# rx_board.net
KiCad netlist of a schematic drawn in Altium Designer
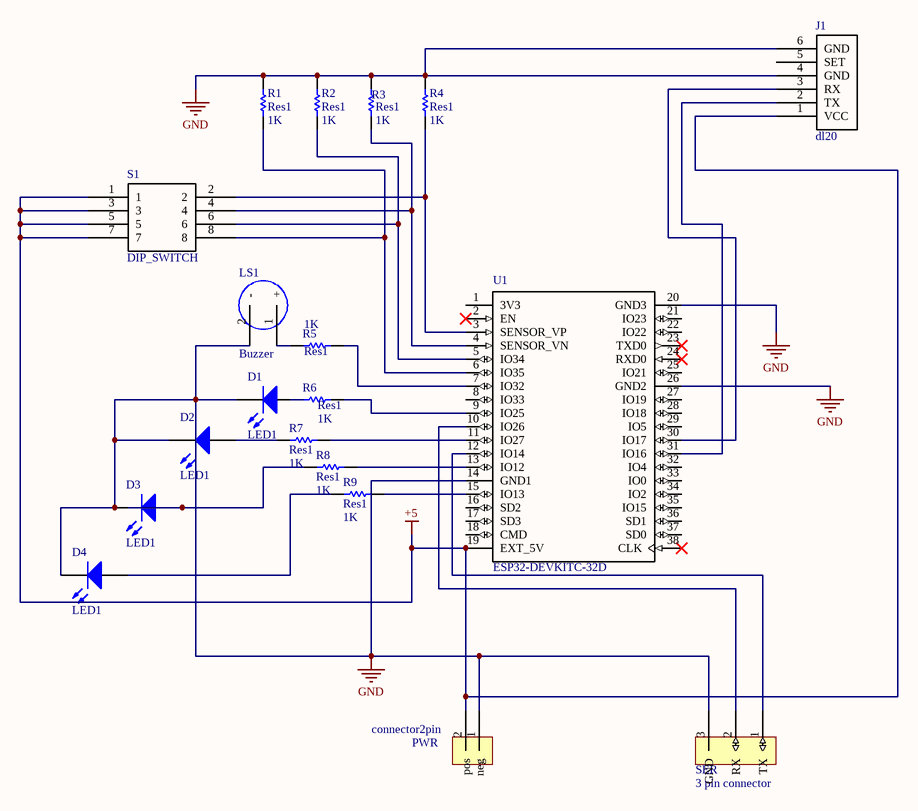
[diagram p0: rx_board.SchDoc]

(export (version "E")
  (design (tool "Eeschema 10.0.6"))
  (components
    (comp (ref "D1")
      (value "LED1")
      (footprint "led3mm")
      (description "Typical RED GaAs LED")
      (fields (field (name "PUBLISHER") "Altium Limited"))
      (libsource (lib "Miscellaneous Devices") (part "LED1"))
    )
    (comp (ref "D2")
      (value "LED1")
      (footprint "led3mm")
      (description "Typical RED GaAs LED")
      (fields (field (name "PUBLISHER") "Altium Limited"))
      (libsource (lib "Miscellaneous Devices") (part "LED1"))
    )
    (comp (ref "D3")
      (value "LED1")
      (footprint "led3mm")
      (description "Typical RED GaAs LED")
      (fields (field (name "PUBLISHER") "Altium Limited"))
      (libsource (lib "Miscellaneous Devices") (part "LED1"))
    )
    (comp (ref "D4")
      (value "LED1")
      (footprint "led3mm")
      (description "Typical RED GaAs LED")
      (fields (field (name "PUBLISHER") "Altium Limited"))
      (libsource (lib "Miscellaneous Devices") (part "LED1"))
    )
    (comp (ref "J1") (value "dl20") (footprint "DL20") (libsource (lib "Schlib1") (part "dl20")))
    (comp (ref "LS1") (value "Buzzer") (footprint "buzzer") (libsource (lib "Buzzer") (part "Buzzer")))
    (comp (ref "PWR")
      (value "connector2pin")
      (footprint "connector2pin")
      (libsource (lib "connector2pin") (part "connector2pin"))
    )
    (comp (ref "R1")
      (value "Res1")
      (footprint "J1-0603")
      (description "Resistor")
      (fields (field (name "ALTIUM_VALUE") "1K") (field (name "PUBLISHER") "Altium Limited"))
      (libsource (lib "Miscellaneous Devices") (part "Res1"))
    )
    (comp (ref "R2")
      (value "Res1")
      (footprint "J1-0603")
      (description "Resistor")
      (fields (field (name "ALTIUM_VALUE") "1K") (field (name "PUBLISHER") "Altium Limited"))
      (libsource (lib "Miscellaneous Devices") (part "Res1"))
    )
    (comp (ref "R3")
      (value "Res1")
      (footprint "J1-0603")
      (description "Resistor")
      (fields (field (name "ALTIUM_VALUE") "1K") (field (name "PUBLISHER") "Altium Limited"))
      (libsource (lib "Miscellaneous Devices") (part "Res1"))
    )
    (comp (ref "R4")
      (value "Res1")
      (footprint "J1-0603")
      (description "Resistor")
      (fields (field (name "ALTIUM_VALUE") "1K") (field (name "PUBLISHER") "Altium Limited"))
      (libsource (lib "Miscellaneous Devices") (part "Res1"))
    )
    (comp (ref "R5")
      (value "Res1")
      (footprint "J1-0603")
      (description "Resistor")
      (fields (field (name "ALTIUM_VALUE") "1K") (field (name "PUBLISHER") "Altium Limited"))
      (libsource (lib "Miscellaneous Devices") (part "Res1"))
    )
    (comp (ref "R6")
      (value "Res1")
      (footprint "J1-0603")
      (description "Resistor")
      (fields (field (name "ALTIUM_VALUE") "1K") (field (name "PUBLISHER") "Altium Limited"))
      (libsource (lib "Miscellaneous Devices") (part "Res1"))
    )
    (comp (ref "R7")
      (value "Res1")
      (footprint "J1-0603")
      (description "Resistor")
      (fields (field (name "ALTIUM_VALUE") "1K") (field (name "PUBLISHER") "Altium Limited"))
      (libsource (lib "Miscellaneous Devices") (part "Res1"))
    )
    (comp (ref "R8")
      (value "Res1")
      (footprint "J1-0603")
      (description "Resistor")
      (fields (field (name "ALTIUM_VALUE") "1K") (field (name "PUBLISHER") "Altium Limited"))
      (libsource (lib "Miscellaneous Devices") (part "Res1"))
    )
    (comp (ref "R9")
      (value "Res1")
      (footprint "J1-0603")
      (description "Resistor")
      (fields (field (name "ALTIUM_VALUE") "1K") (field (name "PUBLISHER") "Altium Limited"))
      (libsource (lib "Miscellaneous Devices") (part "Res1"))
    )
    (comp (ref "S1")
      (value "DIP_SWITCH")
      (footprint "DIP_SWITCH_4_SPST")
      (libsource (lib "Schlib1") (part "DIP_SWITCH"))
    )
    (comp (ref "SER")
      (value "3 pin connector")
      (footprint "connector3pin")
      (libsource (lib "CONNECTOR3PIN") (part "CONNECTOR3PIN"))
    )
    (comp (ref "U1")
      (value "ESP32-DEVKITC-32D")
      (footprint "MODULE_ESP32-DEVKITC-32D")
      (description "Eval Board For Esp-Wroom-32")
      (fields (field (name "MF") "Espressif Systems"))
      (libsource (lib "ESP32-DEVKITC-32D") (part "ESP32-DEVKITC-32D"))
    )
  )
  (nets
    (net (code "1") (name "+5") (class "Default")
      (node (ref "J1") (pin "1") (pinfunction "VCC_1") (pintype "power_in"))
      (node (ref "PWR") (pin "2") (pinfunction "pos_2") (pintype "power_in"))
      (node (ref "S1") (pin "1") (pinfunction "1_1") (pintype "passive"))
      (node (ref "S1") (pin "3") (pinfunction "3_3") (pintype "passive"))
      (node (ref "S1") (pin "5") (pinfunction "5_5") (pintype "passive"))
      (node (ref "S1") (pin "7") (pinfunction "7_7") (pintype "passive"))
      (node (ref "U1") (pin "19") (pinfunction "EXT_5V_19") (pintype "power_in"))
    )
    (net (code "2") (name "GND") (class "Default")
      (node (ref "D1") (pin "2") (pinfunction "K_2") (pintype "passive"))
      (node (ref "D2") (pin "2") (pinfunction "K_2") (pintype "passive"))
      (node (ref "D3") (pin "2") (pinfunction "K_2") (pintype "passive"))
      (node (ref "D4") (pin "2") (pinfunction "K_2") (pintype "passive"))
      (node (ref "J1") (pin "4") (pinfunction "GND_4") (pintype "power_in"))
      (node (ref "J1") (pin "6") (pinfunction "GND_6") (pintype "power_in"))
      (node (ref "LS1") (pin "2") (pinfunction "-_2") (pintype "power_in"))
      (node (ref "PWR") (pin "1") (pinfunction "neg_1") (pintype "power_in"))
      (node (ref "R1") (pin "1") (pinfunction "1_1") (pintype "passive"))
      (node (ref "R2") (pin "1") (pinfunction "1_1") (pintype "passive"))
      (node (ref "R3") (pin "1") (pinfunction "1_1") (pintype "passive"))
      (node (ref "R4") (pin "1") (pinfunction "1_1") (pintype "passive"))
      (node (ref "SER") (pin "3") (pinfunction "GND_3") (pintype "power_in"))
      (node (ref "U1") (pin "14") (pinfunction "GND1_14") (pintype "power_in"))
      (node (ref "U1") (pin "20") (pinfunction "GND3_20") (pintype "power_in"))
      (node (ref "U1") (pin "26") (pinfunction "GND2_26") (pintype "power_in"))
    )
    (net (code "3") (name "Net-(D1-A)") (class "Default")
      (node (ref "D1") (pin "1") (pinfunction "A_1") (pintype "passive"))
      (node (ref "R6") (pin "1") (pinfunction "1_1") (pintype "passive"))
    )
    (net (code "4") (name "Net-(D2-A)") (class "Default")
      (node (ref "D2") (pin "1") (pinfunction "A_1") (pintype "passive"))
      (node (ref "R7") (pin "1") (pinfunction "1_1") (pintype "passive"))
    )
    (net (code "5") (name "Net-(D3-A)") (class "Default")
      (node (ref "D3") (pin "1") (pinfunction "A_1") (pintype "passive"))
      (node (ref "R8") (pin "1") (pinfunction "1_1") (pintype "passive"))
    )
    (net (code "6") (name "Net-(D4-A)") (class "Default")
      (node (ref "D4") (pin "1") (pinfunction "A_1") (pintype "passive"))
      (node (ref "R9") (pin "1") (pinfunction "1_1") (pintype "passive"))
    )
    (net (code "7") (name "Net-(J1-RX)") (class "Default")
      (node (ref "J1") (pin "3") (pinfunction "RX_3") (pintype "passive"))
      (node (ref "U1") (pin "30") (pinfunction "IO17_30") (pintype "bidirectional"))
    )
    (net (code "8") (name "Net-(J1-TX)") (class "Default")
      (node (ref "J1") (pin "2") (pinfunction "TX_2") (pintype "passive"))
      (node (ref "U1") (pin "31") (pinfunction "IO16_31") (pintype "bidirectional"))
    )
    (net (code "9") (name "Net-(LS1-+)") (class "Default")
      (node (ref "LS1") (pin "1") (pinfunction "+_1") (pintype "power_in"))
      (node (ref "R5") (pin "1") (pinfunction "1_1") (pintype "passive"))
    )
    (net (code "10") (name "Net-(SER-RX)") (class "Default")
      (node (ref "SER") (pin "2") (pinfunction "RX_2") (pintype "bidirectional"))
      (node (ref "U1") (pin "10") (pinfunction "IO26_10") (pintype "bidirectional"))
    )
    (net (code "11") (name "Net-(SER-TX)") (class "Default")
      (node (ref "SER") (pin "1") (pinfunction "TX_1") (pintype "bidirectional"))
      (node (ref "U1") (pin "12") (pinfunction "IO14_12") (pintype "bidirectional"))
    )
    (net (code "12") (name "Net-(U1-IO12)") (class "Default")
      (node (ref "R8") (pin "2") (pinfunction "2_2") (pintype "passive"))
      (node (ref "U1") (pin "13") (pinfunction "IO12_13") (pintype "bidirectional"))
    )
    (net (code "13") (name "Net-(U1-IO13)") (class "Default")
      (node (ref "R9") (pin "2") (pinfunction "2_2") (pintype "passive"))
      (node (ref "U1") (pin "15") (pinfunction "IO13_15") (pintype "bidirectional"))
    )
    (net (code "14") (name "Net-(U1-IO25)") (class "Default")
      (node (ref "R6") (pin "2") (pinfunction "2_2") (pintype "passive"))
      (node (ref "U1") (pin "9") (pinfunction "IO25_9") (pintype "bidirectional"))
    )
    (net (code "15") (name "Net-(U1-IO27)") (class "Default")
      (node (ref "R7") (pin "2") (pinfunction "2_2") (pintype "passive"))
      (node (ref "U1") (pin "11") (pinfunction "IO27_11") (pintype "bidirectional"))
    )
    (net (code "16") (name "Net-(U1-IO32)") (class "Default")
      (node (ref "R5") (pin "2") (pinfunction "2_2") (pintype "passive"))
      (node (ref "U1") (pin "7") (pinfunction "IO32_7") (pintype "bidirectional"))
    )
    (net (code "17") (name "Net-(U1-IO34)") (class "Default")
      (node (ref "R2") (pin "2") (pinfunction "2_2") (pintype "passive"))
      (node (ref "S1") (pin "6") (pinfunction "6_6") (pintype "passive"))
      (node (ref "U1") (pin "5") (pinfunction "IO34_5") (pintype "bidirectional"))
    )
    (net (code "18") (name "Net-(U1-IO35)") (class "Default")
      (node (ref "R1") (pin "2") (pinfunction "2_2") (pintype "passive"))
      (node (ref "S1") (pin "8") (pinfunction "8_8") (pintype "passive"))
      (node (ref "U1") (pin "6") (pinfunction "IO35_6") (pintype "bidirectional"))
    )
    (net (code "19") (name "Net-(U1-SENSOR_VN)") (class "Default")
      (node (ref "R3") (pin "2") (pinfunction "2_2") (pintype "passive"))
      (node (ref "S1") (pin "4") (pinfunction "4_4") (pintype "passive"))
      (node (ref "U1") (pin "4") (pinfunction "SENSOR_VN_4") (pintype "input"))
    )
    (net (code "20") (name "Net-(U1-SENSOR_VP)") (class "Default")
      (node (ref "R4") (pin "2") (pinfunction "2_2") (pintype "passive"))
      (node (ref "S1") (pin "2") (pinfunction "2_2") (pintype "passive"))
      (node (ref "U1") (pin "3") (pinfunction "SENSOR_VP_3") (pintype "input"))
    )
    (net (code "21") (name "unconnected-(J1-SET-Pad5)") (class "Default")
      (node (ref "J1") (pin "5") (pinfunction "SET_5") (pintype "passive"))
    )
    (net (code "22") (name "unconnected-(U1-3V3-Pad1)") (class "Default")
      (node (ref "U1") (pin "1") (pinfunction "3V3_1") (pintype "power_in"))
    )
    (net (code "23") (name "unconnected-(U1-CLK-Pad38)") (class "Default")
      (node (ref "U1") (pin "38") (pinfunction "CLK_38") (pintype "input+no_connect"))
    )
    (net (code "24") (name "unconnected-(U1-CMD-Pad18)") (class "Default")
      (node (ref "U1") (pin "18") (pinfunction "CMD_18") (pintype "bidirectional"))
    )
    (net (code "25") (name "unconnected-(U1-EN-Pad2)") (class "Default")
      (node (ref "U1") (pin "2") (pinfunction "EN_2") (pintype "input+no_connect"))
    )
    (net (code "26") (name "unconnected-(U1-IO0-Pad33)") (class "Default")
      (node (ref "U1") (pin "33") (pinfunction "IO0_33") (pintype "bidirectional"))
    )
    (net (code "27") (name "unconnected-(U1-IO2-Pad34)") (class "Default")
      (node (ref "U1") (pin "34") (pinfunction "IO2_34") (pintype "bidirectional"))
    )
    (net (code "28") (name "unconnected-(U1-IO4-Pad32)") (class "Default")
      (node (ref "U1") (pin "32") (pinfunction "IO4_32") (pintype "bidirectional"))
    )
    (net (code "29") (name "unconnected-(U1-IO5-Pad29)") (class "Default")
      (node (ref "U1") (pin "29") (pinfunction "IO5_29") (pintype "bidirectional"))
    )
    (net (code "30") (name "unconnected-(U1-IO15-Pad35)") (class "Default")
      (node (ref "U1") (pin "35") (pinfunction "IO15_35") (pintype "bidirectional"))
    )
    (net (code "31") (name "unconnected-(U1-IO18-Pad28)") (class "Default")
      (node (ref "U1") (pin "28") (pinfunction "IO18_28") (pintype "bidirectional"))
    )
    (net (code "32") (name "unconnected-(U1-IO19-Pad27)") (class "Default")
      (node (ref "U1") (pin "27") (pinfunction "IO19_27") (pintype "bidirectional"))
    )
    (net (code "33") (name "unconnected-(U1-IO21-Pad25)") (class "Default")
      (node (ref "U1") (pin "25") (pinfunction "IO21_25") (pintype "bidirectional"))
    )
    (net (code "34") (name "unconnected-(U1-IO22-Pad22)") (class "Default")
      (node (ref "U1") (pin "22") (pinfunction "IO22_22") (pintype "bidirectional"))
    )
    (net (code "35") (name "unconnected-(U1-IO23-Pad21)") (class "Default")
      (node (ref "U1") (pin "21") (pinfunction "IO23_21") (pintype "bidirectional"))
    )
    (net (code "36") (name "unconnected-(U1-IO33-Pad8)") (class "Default")
      (node (ref "U1") (pin "8") (pinfunction "IO33_8") (pintype "bidirectional"))
    )
    (net (code "37") (name "unconnected-(U1-RXD0-Pad24)") (class "Default")
      (node (ref "U1") (pin "24") (pinfunction "RXD0_24") (pintype "input+no_connect"))
    )
    (net (code "38") (name "unconnected-(U1-SD0-Pad37)") (class "Default")
      (node (ref "U1") (pin "37") (pinfunction "SD0_37") (pintype "bidirectional"))
    )
    (net (code "39") (name "unconnected-(U1-SD1-Pad36)") (class "Default")
      (node (ref "U1") (pin "36") (pinfunction "SD1_36") (pintype "bidirectional"))
    )
    (net (code "40") (name "unconnected-(U1-SD2-Pad16)") (class "Default")
      (node (ref "U1") (pin "16") (pinfunction "SD2_16") (pintype "bidirectional"))
    )
    (net (code "41") (name "unconnected-(U1-SD3-Pad17)") (class "Default")
      (node (ref "U1") (pin "17") (pinfunction "SD3_17") (pintype "bidirectional"))
    )
    (net (code "42") (name "unconnected-(U1-TXD0-Pad23)") (class "Default")
      (node (ref "U1") (pin "23") (pinfunction "TXD0_23") (pintype "output+no_connect"))
    )
  )
)
